# rapidshark-display-shifter-mk-3_0.net
KiCad netlist of a schematic drawn in EAGLE
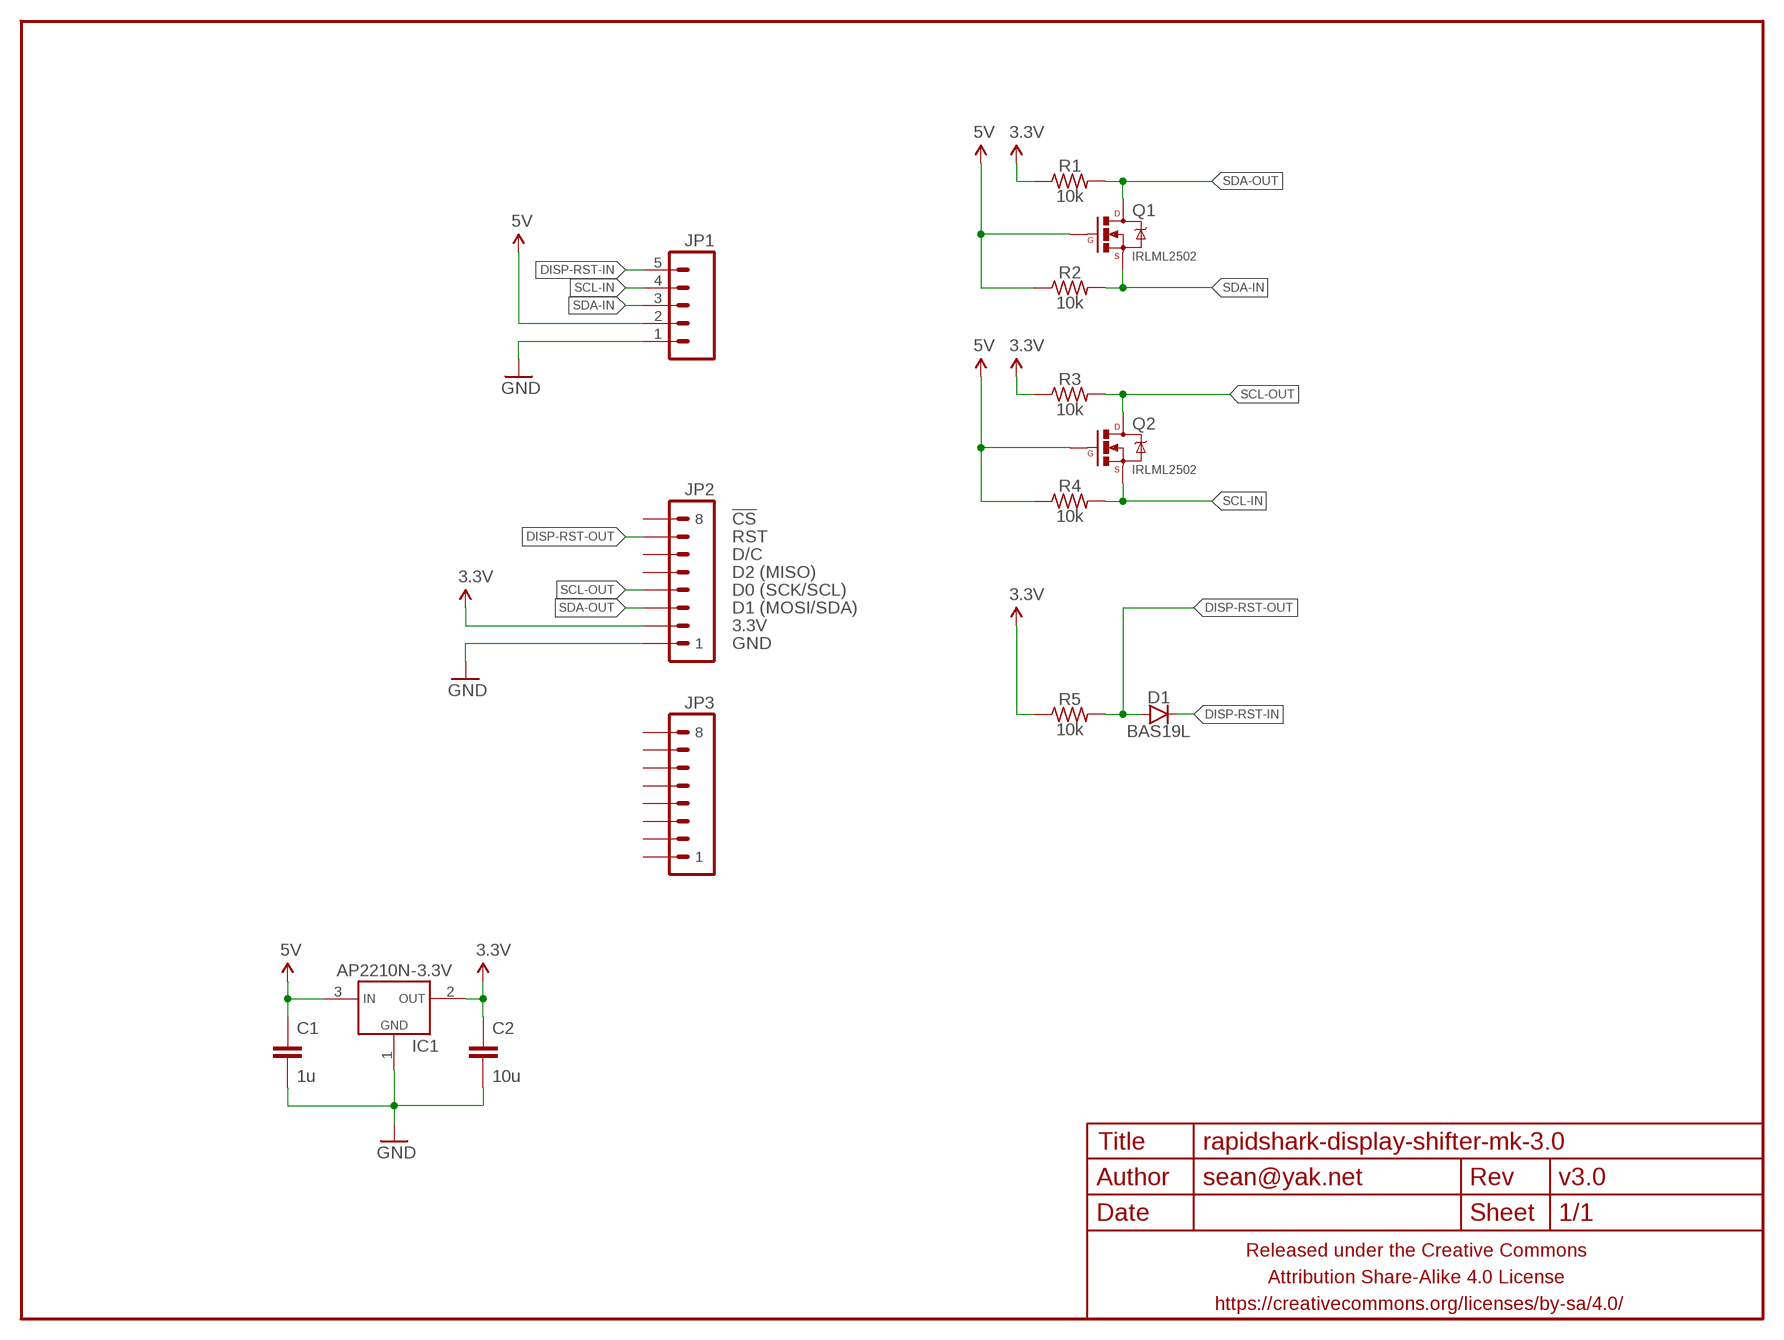
[diagram p0: schematic, sheet 1]

(export (version "E")
  (design (tool "Eeschema 10.0.6"))
  (components
    (comp (ref "C1")
      (value "1u")
      (footprint "eagle-import:C0805")
      (libsource (lib "eagle-import") (part "CAPACITOR-CERAMICC0805"))
    )
    (comp (ref "C2")
      (value "10u")
      (footprint "eagle-import:C0805")
      (libsource (lib "eagle-import") (part "CAPACITOR-CERAMICC0805"))
    )
    (comp (ref "D1")
      (value "BAS19L")
      (footprint "eagle-import:SOT23")
      (libsource (lib "eagle-import") (part "DIODESOT23"))
    )
    (comp (ref "FRAME1")
      (value "FRAME-LETTERNO_PACKAGE")
      (footprint "eagle-import:DUMMY")
      (fields (field (name "DESIGNER") "sean@yak.net") (field (name "VERSION") "v3.0"))
      (libsource (lib "eagle-import") (part "FRAME-LETTERNO_PACKAGE"))
    )
    (comp (ref "IC1")
      (value "AP2210N-3.3V")
      (footprint "eagle-import:SOT23")
      (libsource (lib "eagle-import") (part "VREG_1117SOT-23"))
    )
    (comp (ref "JP1")
      (value "M05PTH-CENTERED")
      (footprint "eagle-import:1X05_PTH_CENTERED")
      (libsource (lib "eagle-import") (part "M05PTH-CENTERED"))
    )
    (comp (ref "JP2")
      (value "M081X08")
      (footprint "eagle-import:1X08")
      (libsource (lib "eagle-import") (part "M081X08"))
    )
    (comp (ref "JP3")
      (value "M081X08")
      (footprint "eagle-import:1X08")
      (libsource (lib "eagle-import") (part "M081X08"))
    )
    (comp (ref "Q1")
      (value "IRLML2502")
      (footprint "eagle-import:SOT23")
      (libsource (lib "eagle-import") (part "MOSFET-NCHANNELIRLML2502"))
    )
    (comp (ref "Q2")
      (value "IRLML2502")
      (footprint "eagle-import:SOT23")
      (libsource (lib "eagle-import") (part "MOSFET-NCHANNELIRLML2502"))
    )
    (comp (ref "R1")
      (value "10k")
      (footprint "eagle-import:R0603")
      (libsource (lib "eagle-import") (part "RESISTORR0603"))
    )
    (comp (ref "R2")
      (value "10k")
      (footprint "eagle-import:R0603")
      (libsource (lib "eagle-import") (part "RESISTORR0603"))
    )
    (comp (ref "R3")
      (value "10k")
      (footprint "eagle-import:R0603")
      (libsource (lib "eagle-import") (part "RESISTORR0603"))
    )
    (comp (ref "R4")
      (value "10k")
      (footprint "eagle-import:R0603")
      (libsource (lib "eagle-import") (part "RESISTORR0603"))
    )
    (comp (ref "R5")
      (value "10k")
      (footprint "eagle-import:R0603")
      (libsource (lib "eagle-import") (part "RESISTORR0603"))
    )
  )
  (nets
    (net (code "1") (name "3.3V") (class "Default")
      (node (ref "C2") (pin "1") (pinfunction "1_1") (pintype "passive"))
      (node (ref "IC1") (pin "2") (pinfunction "VOUT_2") (pintype "bidirectional"))
      (node (ref "JP2") (pin "2") (pinfunction "2_2") (pintype "passive"))
      (node (ref "R1") (pin "1") (pinfunction "1_1") (pintype "passive"))
      (node (ref "R3") (pin "1") (pinfunction "1_1") (pintype "passive"))
      (node (ref "R5") (pin "1") (pinfunction "1_1") (pintype "passive"))
    )
    (net (code "2") (name "5V") (class "Default")
      (node (ref "C1") (pin "1") (pinfunction "1_1") (pintype "passive"))
      (node (ref "IC1") (pin "3") (pinfunction "VIN_3") (pintype "bidirectional"))
      (node (ref "JP1") (pin "2") (pinfunction "2_2") (pintype "passive"))
      (node (ref "Q1") (pin "1") (pinfunction "G_1") (pintype "passive"))
      (node (ref "Q2") (pin "1") (pinfunction "G_1") (pintype "passive"))
      (node (ref "R2") (pin "1") (pinfunction "1_1") (pintype "passive"))
      (node (ref "R4") (pin "1") (pinfunction "1_1") (pintype "passive"))
    )
    (net (code "3") (name "DISP-RST-IN") (class "Default")
      (node (ref "D1") (pin "3") (pinfunction "C_3") (pintype "passive"))
      (node (ref "JP1") (pin "5") (pinfunction "5_5") (pintype "passive"))
    )
    (net (code "4") (name "DISP-RST-OUT") (class "Default")
      (node (ref "D1") (pin "1") (pinfunction "A_1") (pintype "passive"))
      (node (ref "JP2") (pin "7") (pinfunction "7_7") (pintype "passive"))
      (node (ref "R5") (pin "2") (pinfunction "2_2") (pintype "passive"))
    )
    (net (code "5") (name "GND") (class "Default")
      (node (ref "C1") (pin "2") (pinfunction "2_2") (pintype "passive"))
      (node (ref "C2") (pin "2") (pinfunction "2_2") (pintype "passive"))
      (node (ref "IC1") (pin "1") (pinfunction "GND_1") (pintype "bidirectional"))
      (node (ref "JP1") (pin "1") (pinfunction "1_1") (pintype "passive"))
      (node (ref "JP2") (pin "1") (pinfunction "1_1") (pintype "passive"))
    )
    (net (code "6") (name "SCL-IN") (class "Default")
      (node (ref "JP1") (pin "4") (pinfunction "4_4") (pintype "passive"))
      (node (ref "Q2") (pin "2") (pinfunction "S_2") (pintype "passive"))
      (node (ref "R4") (pin "2") (pinfunction "2_2") (pintype "passive"))
    )
    (net (code "7") (name "SCL-OUT") (class "Default")
      (node (ref "JP2") (pin "4") (pinfunction "4_4") (pintype "passive"))
      (node (ref "Q2") (pin "3") (pinfunction "D_3") (pintype "passive"))
      (node (ref "R3") (pin "2") (pinfunction "2_2") (pintype "passive"))
    )
    (net (code "8") (name "SDA-IN") (class "Default")
      (node (ref "JP1") (pin "3") (pinfunction "3_3") (pintype "passive"))
      (node (ref "Q1") (pin "2") (pinfunction "S_2") (pintype "passive"))
      (node (ref "R2") (pin "2") (pinfunction "2_2") (pintype "passive"))
    )
    (net (code "9") (name "SDA-OUT") (class "Default")
      (node (ref "JP2") (pin "3") (pinfunction "3_3") (pintype "passive"))
      (node (ref "Q1") (pin "3") (pinfunction "D_3") (pintype "passive"))
      (node (ref "R1") (pin "2") (pinfunction "2_2") (pintype "passive"))
    )
    (net (code "10") (name "unconnected-(JP2-Pad5)") (class "Default")
      (node (ref "JP2") (pin "5") (pinfunction "5_5") (pintype "passive"))
    )
    (net (code "11") (name "unconnected-(JP2-Pad6)") (class "Default")
      (node (ref "JP2") (pin "6") (pinfunction "6_6") (pintype "passive"))
    )
    (net (code "12") (name "unconnected-(JP2-Pad8)") (class "Default")
      (node (ref "JP2") (pin "8") (pinfunction "8_8") (pintype "passive"))
    )
    (net (code "13") (name "unconnected-(JP3-Pad1)") (class "Default")
      (node (ref "JP3") (pin "1") (pinfunction "1_1") (pintype "passive"))
    )
    (net (code "14") (name "unconnected-(JP3-Pad2)") (class "Default")
      (node (ref "JP3") (pin "2") (pinfunction "2_2") (pintype "passive"))
    )
    (net (code "15") (name "unconnected-(JP3-Pad3)") (class "Default")
      (node (ref "JP3") (pin "3") (pinfunction "3_3") (pintype "passive"))
    )
    (net (code "16") (name "unconnected-(JP3-Pad4)") (class "Default")
      (node (ref "JP3") (pin "4") (pinfunction "4_4") (pintype "passive"))
    )
    (net (code "17") (name "unconnected-(JP3-Pad5)") (class "Default")
      (node (ref "JP3") (pin "5") (pinfunction "5_5") (pintype "passive"))
    )
    (net (code "18") (name "unconnected-(JP3-Pad6)") (class "Default")
      (node (ref "JP3") (pin "6") (pinfunction "6_6") (pintype "passive"))
    )
    (net (code "19") (name "unconnected-(JP3-Pad7)") (class "Default")
      (node (ref "JP3") (pin "7") (pinfunction "7_7") (pintype "passive"))
    )
    (net (code "20") (name "unconnected-(JP3-Pad8)") (class "Default")
      (node (ref "JP3") (pin "8") (pinfunction "8_8") (pintype "passive"))
    )
  )
)
